# LEDPCB.net
KiCad netlist of a schematic drawn in EAGLE
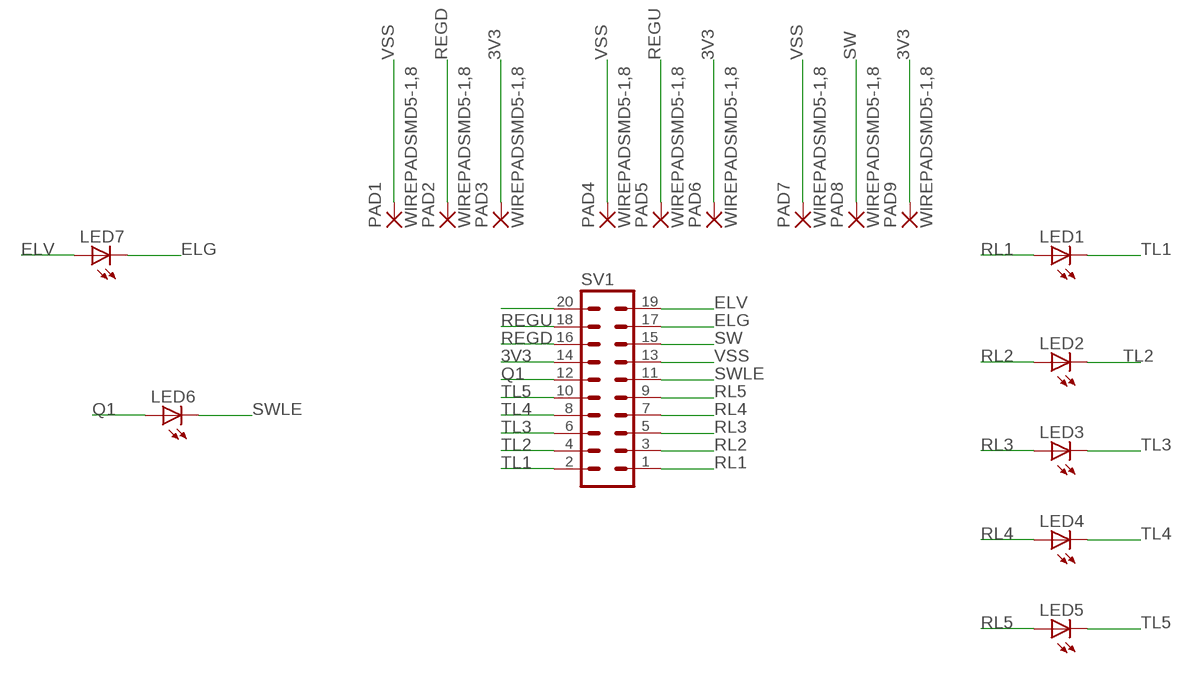
[diagram p0: schematic, sheet 1]

(export (version "E")
  (design (tool "Eeschema 10.0.6"))
  (components
    (comp (ref "LED1")
      (value "LEDSMT1206")
      (footprint "eagle-import:1206")
      (libsource (lib "eagle-import") (part "LEDSMT1206"))
    )
    (comp (ref "LED2")
      (value "LEDSMT1206")
      (footprint "eagle-import:1206")
      (libsource (lib "eagle-import") (part "LEDSMT1206"))
    )
    (comp (ref "LED3")
      (value "LEDSMT1206")
      (footprint "eagle-import:1206")
      (libsource (lib "eagle-import") (part "LEDSMT1206"))
    )
    (comp (ref "LED4")
      (value "LEDSMT1206")
      (footprint "eagle-import:1206")
      (libsource (lib "eagle-import") (part "LEDSMT1206"))
    )
    (comp (ref "LED5")
      (value "LEDSMT1206")
      (footprint "eagle-import:1206")
      (libsource (lib "eagle-import") (part "LEDSMT1206"))
    )
    (comp (ref "LED6")
      (value "LEDSMT1206")
      (footprint "eagle-import:1206")
      (libsource (lib "eagle-import") (part "LEDSMT1206"))
    )
    (comp (ref "LED7")
      (value "LEDSMT1206")
      (footprint "eagle-import:1206")
      (libsource (lib "eagle-import") (part "LEDSMT1206"))
    )
    (comp (ref "PAD1")
      (value "WIREPADSMD5-1,8")
      (footprint "eagle-import:5-1,8")
      (libsource (lib "eagle-import") (part "WIREPADSMD5-1,8"))
    )
    (comp (ref "PAD2")
      (value "WIREPADSMD5-1,8")
      (footprint "eagle-import:5-1,8")
      (libsource (lib "eagle-import") (part "WIREPADSMD5-1,8"))
    )
    (comp (ref "PAD3")
      (value "WIREPADSMD5-1,8")
      (footprint "eagle-import:5-1,8")
      (libsource (lib "eagle-import") (part "WIREPADSMD5-1,8"))
    )
    (comp (ref "PAD4")
      (value "WIREPADSMD5-1,8")
      (footprint "eagle-import:5-1,8")
      (libsource (lib "eagle-import") (part "WIREPADSMD5-1,8"))
    )
    (comp (ref "PAD5")
      (value "WIREPADSMD5-1,8")
      (footprint "eagle-import:5-1,8")
      (libsource (lib "eagle-import") (part "WIREPADSMD5-1,8"))
    )
    (comp (ref "PAD6")
      (value "WIREPADSMD5-1,8")
      (footprint "eagle-import:5-1,8")
      (libsource (lib "eagle-import") (part "WIREPADSMD5-1,8"))
    )
    (comp (ref "PAD7")
      (value "WIREPADSMD5-1,8")
      (footprint "eagle-import:5-1,8")
      (libsource (lib "eagle-import") (part "WIREPADSMD5-1,8"))
    )
    (comp (ref "PAD8")
      (value "WIREPADSMD5-1,8")
      (footprint "eagle-import:5-1,8")
      (libsource (lib "eagle-import") (part "WIREPADSMD5-1,8"))
    )
    (comp (ref "PAD9")
      (value "WIREPADSMD5-1,8")
      (footprint "eagle-import:5-1,8")
      (libsource (lib "eagle-import") (part "WIREPADSMD5-1,8"))
    )
    (comp (ref "SV1")
      (value "MA10-2")
      (footprint "eagle-import:MA10-2")
      (libsource (lib "eagle-import") (part "MA10-2"))
    )
  )
  (nets
    (net (code "1") (name "/3V3") (class "Default")
      (node (ref "PAD3") (pin "1") (pinfunction "P_1") (pintype "passive"))
      (node (ref "PAD6") (pin "1") (pinfunction "P_1") (pintype "passive"))
      (node (ref "PAD9") (pin "1") (pinfunction "P_1") (pintype "passive"))
      (node (ref "SV1") (pin "14") (pinfunction "14_14") (pintype "passive"))
    )
    (net (code "2") (name "/ELG") (class "Default")
      (node (ref "LED7") (pin "C") (pinfunction "C_C") (pintype "passive"))
      (node (ref "SV1") (pin "17") (pinfunction "17_17") (pintype "passive"))
    )
    (net (code "3") (name "/ELV") (class "Default")
      (node (ref "LED7") (pin "A") (pinfunction "A_A") (pintype "passive"))
      (node (ref "SV1") (pin "19") (pinfunction "19_19") (pintype "passive"))
    )
    (net (code "4") (name "/Q1") (class "Default")
      (node (ref "LED6") (pin "A") (pinfunction "A_A") (pintype "passive"))
      (node (ref "SV1") (pin "12") (pinfunction "12_12") (pintype "passive"))
    )
    (net (code "5") (name "/REGD") (class "Default")
      (node (ref "PAD2") (pin "1") (pinfunction "P_1") (pintype "passive"))
      (node (ref "SV1") (pin "16") (pinfunction "16_16") (pintype "passive"))
    )
    (net (code "6") (name "/REGU") (class "Default")
      (node (ref "PAD5") (pin "1") (pinfunction "P_1") (pintype "passive"))
      (node (ref "SV1") (pin "18") (pinfunction "18_18") (pintype "passive"))
    )
    (net (code "7") (name "/RL1") (class "Default")
      (node (ref "LED1") (pin "A") (pinfunction "A_A") (pintype "passive"))
      (node (ref "SV1") (pin "1") (pinfunction "1_1") (pintype "passive"))
    )
    (net (code "8") (name "/RL2") (class "Default")
      (node (ref "LED2") (pin "A") (pinfunction "A_A") (pintype "passive"))
      (node (ref "SV1") (pin "3") (pinfunction "3_3") (pintype "passive"))
    )
    (net (code "9") (name "/RL3") (class "Default")
      (node (ref "LED3") (pin "A") (pinfunction "A_A") (pintype "passive"))
      (node (ref "SV1") (pin "5") (pinfunction "5_5") (pintype "passive"))
    )
    (net (code "10") (name "/RL4") (class "Default")
      (node (ref "LED4") (pin "A") (pinfunction "A_A") (pintype "passive"))
      (node (ref "SV1") (pin "7") (pinfunction "7_7") (pintype "passive"))
    )
    (net (code "11") (name "/RL5") (class "Default")
      (node (ref "LED5") (pin "A") (pinfunction "A_A") (pintype "passive"))
      (node (ref "SV1") (pin "9") (pinfunction "9_9") (pintype "passive"))
    )
    (net (code "12") (name "/SW") (class "Default")
      (node (ref "PAD8") (pin "1") (pinfunction "P_1") (pintype "passive"))
      (node (ref "SV1") (pin "15") (pinfunction "15_15") (pintype "passive"))
    )
    (net (code "13") (name "/SWLE") (class "Default")
      (node (ref "LED6") (pin "C") (pinfunction "C_C") (pintype "passive"))
      (node (ref "SV1") (pin "11") (pinfunction "11_11") (pintype "passive"))
    )
    (net (code "14") (name "/TL1") (class "Default")
      (node (ref "LED1") (pin "C") (pinfunction "C_C") (pintype "passive"))
      (node (ref "SV1") (pin "2") (pinfunction "2_2") (pintype "passive"))
    )
    (net (code "15") (name "/TL2") (class "Default")
      (node (ref "LED2") (pin "C") (pinfunction "C_C") (pintype "passive"))
      (node (ref "SV1") (pin "4") (pinfunction "4_4") (pintype "passive"))
    )
    (net (code "16") (name "/TL3") (class "Default")
      (node (ref "LED3") (pin "C") (pinfunction "C_C") (pintype "passive"))
      (node (ref "SV1") (pin "6") (pinfunction "6_6") (pintype "passive"))
    )
    (net (code "17") (name "/TL4") (class "Default")
      (node (ref "LED4") (pin "C") (pinfunction "C_C") (pintype "passive"))
      (node (ref "SV1") (pin "8") (pinfunction "8_8") (pintype "passive"))
    )
    (net (code "18") (name "/TL5") (class "Default")
      (node (ref "LED5") (pin "C") (pinfunction "C_C") (pintype "passive"))
      (node (ref "SV1") (pin "10") (pinfunction "10_10") (pintype "passive"))
    )
    (net (code "19") (name "/VSS") (class "Default")
      (node (ref "PAD1") (pin "1") (pinfunction "P_1") (pintype "passive"))
      (node (ref "PAD4") (pin "1") (pinfunction "P_1") (pintype "passive"))
      (node (ref "PAD7") (pin "1") (pinfunction "P_1") (pintype "passive"))
      (node (ref "SV1") (pin "13") (pinfunction "13_13") (pintype "passive"))
    )
    (net (code "20") (name "unconnected-(SV1-Pad20)") (class "Default")
      (node (ref "SV1") (pin "20") (pinfunction "20_20") (pintype "passive"))
    )
  )
)
